# DRIVERS_CONNECTORS.net
KiCad netlist of a schematic drawn in Altium Designer
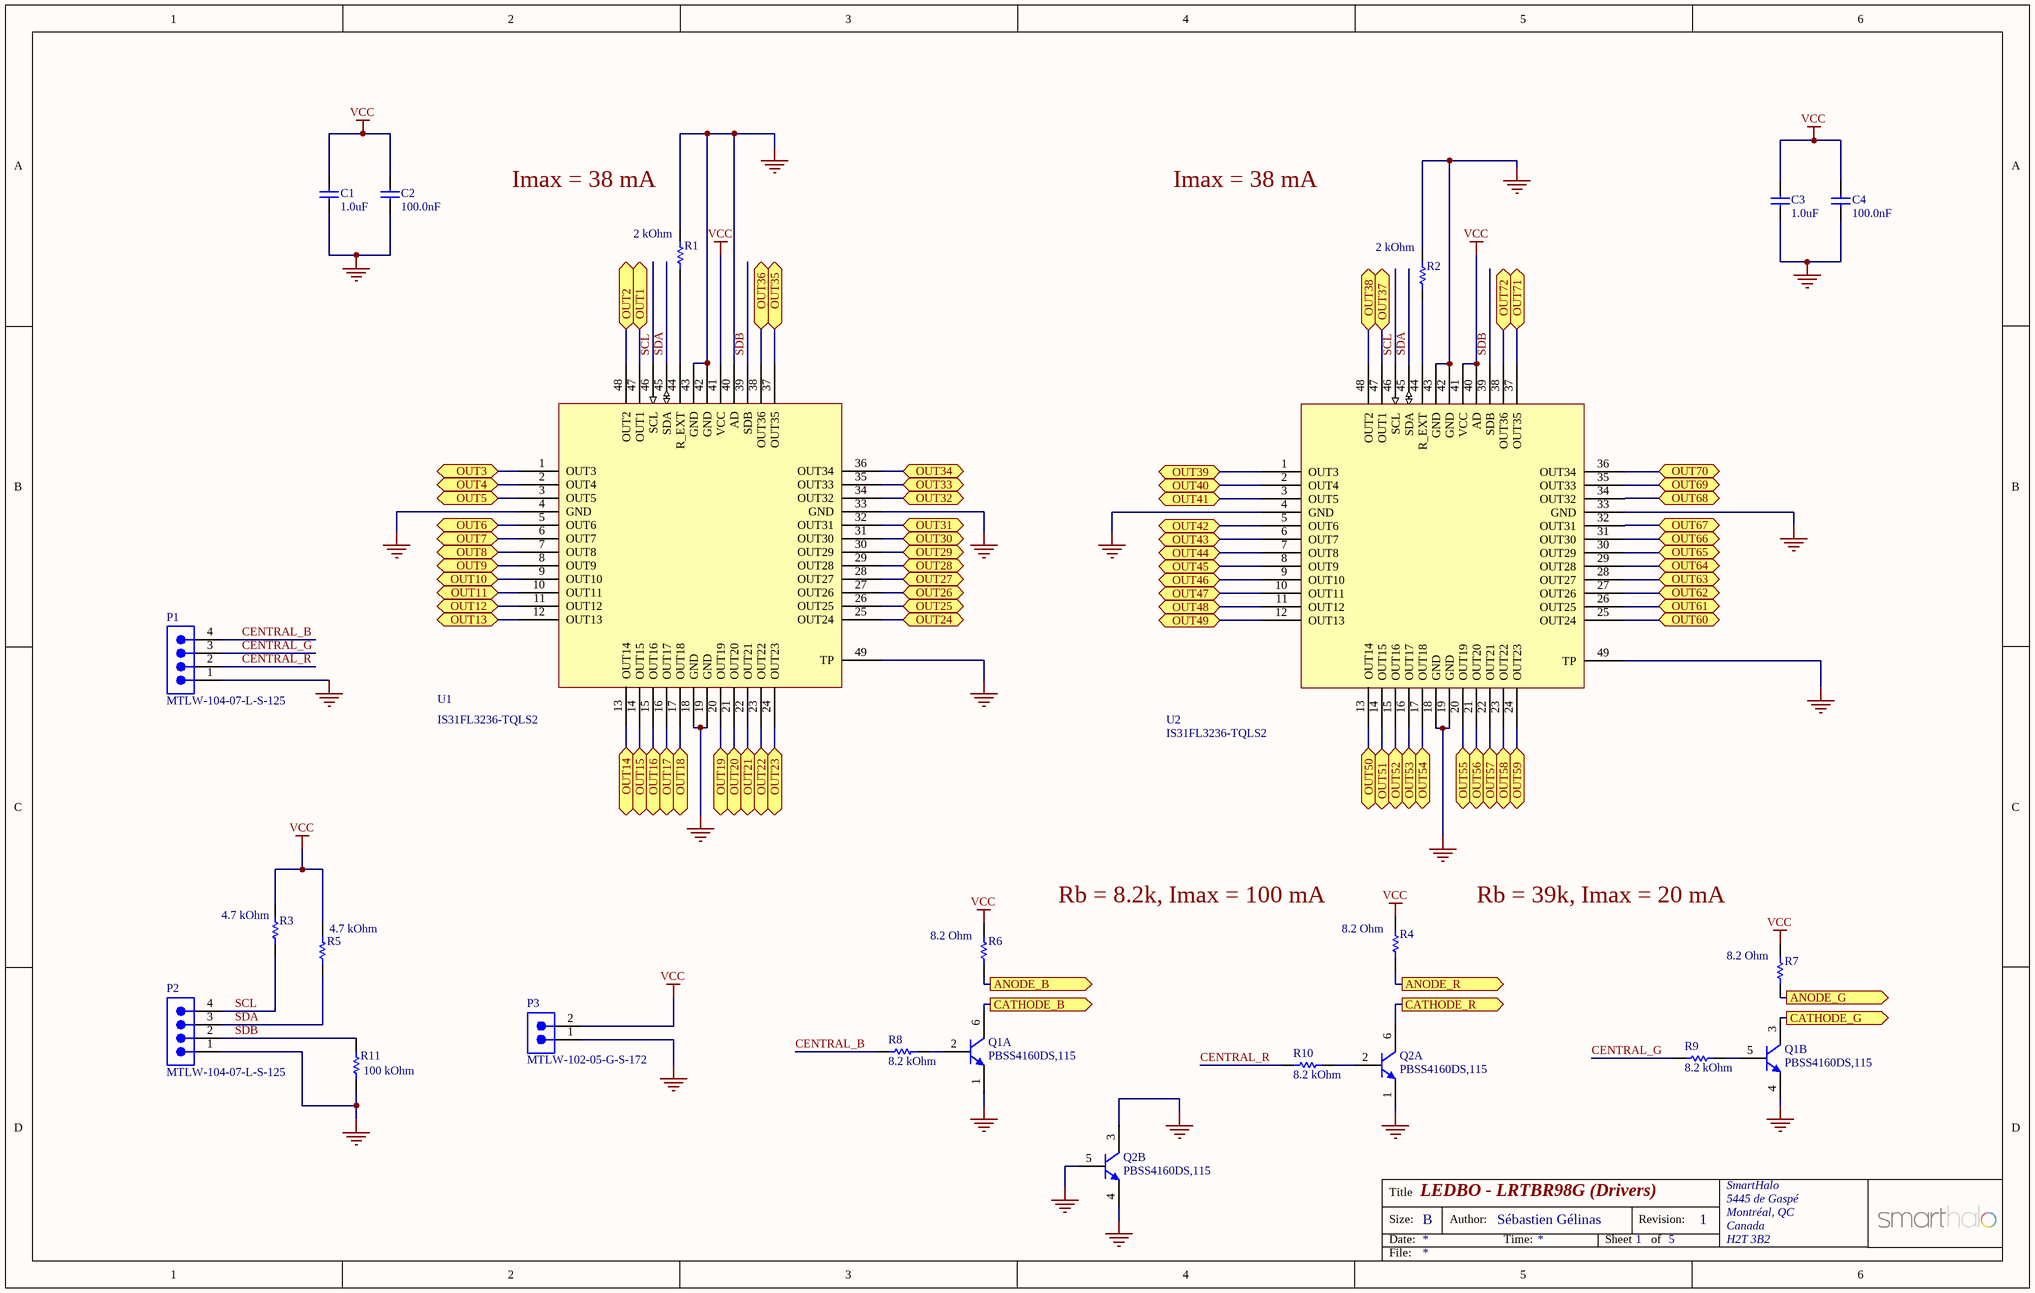
[diagram p0: DRIVERS_CONNECTORS.SchDoc]

(export (version "E")
  (design (tool "Eeschema 10.0.6"))
  (components
    (comp (ref "C1")
      (value "1.0uF")
      (footprint "CAPC0603(1608)100_N")
      (description "Chip Cap 0603 X7R 10%")
      (fields (field (name "PART NUMBER") "C0402-1n0") (field (name "PUBLISHER") "Nordic Semiconductor"))
      (libsource (lib "SmartHalo") (part "CAP0603"))
    )
    (comp (ref "C2")
      (value "100.0nF")
      (footprint "CAPC0603(1608)100_N")
      (description "Chip Cap 0603 X7R 10%")
      (fields (field (name "PART NUMBER") "C0402-1n0") (field (name "PUBLISHER") "Nordic Semiconductor"))
      (libsource (lib "SmartHalo") (part "CAP0603"))
    )
    (comp (ref "C3")
      (value "1.0uF")
      (footprint "CAPC0603(1608)100_N")
      (description "Chip Cap 0603 X7R 10%")
      (fields (field (name "PART NUMBER") "C0402-1n0") (field (name "PUBLISHER") "Nordic Semiconductor"))
      (libsource (lib "SmartHalo") (part "CAP0603"))
    )
    (comp (ref "C4")
      (value "100.0nF")
      (footprint "CAPC0603(1608)100_N")
      (description "Chip Cap 0603 X7R 10%")
      (fields (field (name "PART NUMBER") "C0402-1n0") (field (name "PUBLISHER") "Nordic Semiconductor"))
      (libsource (lib "SmartHalo") (part "CAP0603"))
    )
    (comp (ref "P1")
      (value "MTLW-104-07-L-S-125")
      (footprint "SMTC-MTLW-104-07-X-S-125")
      (fields (field (name "MANUFACTURER") "Samtec"))
      (libsource (lib "Altium Content Vault") (part "CMP-1024-00072-1"))
    )
    (comp (ref "P2")
      (value "MTLW-104-07-L-S-125")
      (footprint "SMTC-MTLW-104-07-X-S-125")
      (fields (field (name "MANUFACTURER") "Samtec"))
      (libsource (lib "Altium Content Vault") (part "CMP-1024-00072-1"))
    )
    (comp (ref "P3")
      (value "MTLW-102-05-G-S-172")
      (footprint "SMTC-MTLW-102-05-X-S-172")
      (fields (field (name "MANUFACTURER") "Samtec"))
      (libsource (lib "Altium Content Vault") (part "CMP-1024-00064-1"))
    )
    (comp (ref "Q1")
      (value "PBSS4160DS,115")
      (footprint "NXP-SC74_M")
      (description "TRANS 2NPN 60V 1A 6TSOP")
      (fields (field (name "PARTNUMBER") "PBSS4160DS") (field (name "MANUFACTURER") "NXP Semiconductors"))
      (libsource (lib "SmartHalo") (part "PBSS4160DS,115"))
    )
    (comp (ref "Q2")
      (value "PBSS4160DS,115")
      (footprint "NXP-SC74_M")
      (description "TRANS 2NPN 60V 1A 6TSOP")
      (fields (field (name "PARTNUMBER") "PBSS4160DS") (field (name "MANUFACTURER") "NXP Semiconductors"))
      (libsource (lib "SmartHalo") (part "PBSS4160DS,115"))
    )
    (comp (ref "R1")
      (value "2 kOhm")
      (footprint "RESC0603(1608)_N")
      (description "2k 0.1W 5% 0603 (1608 Metric)  SMD")
      (fields (field (name "TOLERANCE") "5 %") (field (name "POWER") "0.1 W"))
      (libsource (lib "Altium Content Vault") (part "CMP-1012-00090-1"))
    )
    (comp (ref "R2")
      (value "2 kOhm")
      (footprint "RESC0603(1608)_N")
      (description "2k 0.1W 5% 0603 (1608 Metric)  SMD")
      (fields (field (name "TOLERANCE") "5 %") (field (name "POWER") "0.1 W"))
      (libsource (lib "Altium Content Vault") (part "CMP-1012-00090-1"))
    )
    (comp (ref "R3")
      (value "4.7 kOhm")
      (footprint "RESC0603(1608)_N")
      (description "4K7 0.1W 5% 0603 (1608 Metric)  SMD")
      (fields (field (name "TOLERANCE") "5 %") (field (name "POWER") "0.1 W"))
      (libsource (lib "Altium Content Vault") (part "CMP-1012-00090-1"))
    )
    (comp (ref "R4")
      (value "8.2 Ohm")
      (footprint "RESC0603(1608)_N")
      (description "8R2 0.1W 5% 0603 (1608 Metric)  SMD")
      (fields (field (name "TOLERANCE") "5 %") (field (name "POWER") "0.1 W"))
      (libsource (lib "Altium Content Vault") (part "CMP-1012-00090-1"))
    )
    (comp (ref "R5")
      (value "4.7 kOhm")
      (footprint "RESC0603(1608)_N")
      (description "4K7 0.1W 5% 0603 (1608 Metric)  SMD")
      (fields (field (name "TOLERANCE") "5 %") (field (name "POWER") "0.1 W"))
      (libsource (lib "Altium Content Vault") (part "CMP-1012-00090-1"))
    )
    (comp (ref "R6")
      (value "8.2 Ohm")
      (footprint "RESC0603(1608)_N")
      (description "8R2 0.1W 5% 0603 (1608 Metric)  SMD")
      (fields (field (name "TOLERANCE") "5 %") (field (name "POWER") "0.1 W"))
      (libsource (lib "Altium Content Vault") (part "CMP-1012-00090-1"))
    )
    (comp (ref "R7")
      (value "8.2 Ohm")
      (footprint "RESC0603(1608)_N")
      (description "8R2 0.1W 5% 0603 (1608 Metric)  SMD")
      (fields (field (name "TOLERANCE") "5 %") (field (name "POWER") "0.1 W"))
      (libsource (lib "Altium Content Vault") (part "CMP-1012-00090-1"))
    )
    (comp (ref "R8")
      (value "8.2 kOhm")
      (footprint "RESC0603(1608)_N")
      (description "8K2 0.1W 5% 0603 (1608 Metric)  SMD")
      (fields (field (name "TOLERANCE") "5 %") (field (name "POWER") "0.1 W"))
      (libsource (lib "Altium Content Vault") (part "CMP-1012-00090-1"))
    )
    (comp (ref "R9")
      (value "8.2 kOhm")
      (footprint "RESC0603(1608)_N")
      (description "8K2 0.1W 5% 0603 (1608 Metric)  SMD")
      (fields (field (name "TOLERANCE") "5 %") (field (name "POWER") "0.1 W"))
      (libsource (lib "Altium Content Vault") (part "CMP-1012-00090-1"))
    )
    (comp (ref "R10")
      (value "8.2 kOhm")
      (footprint "RESC0603(1608)_N")
      (description "8K2 0.1W 5% 0603 (1608 Metric)  SMD")
      (fields (field (name "TOLERANCE") "5 %") (field (name "POWER") "0.1 W"))
      (libsource (lib "Altium Content Vault") (part "CMP-1012-00090-1"))
    )
    (comp (ref "R11")
      (value "100 kOhm")
      (footprint "RESC0603(1608)_N")
      (description "100k 0.1W 5% 0603 (1608 Metric)  SMD")
      (fields (field (name "TOLERANCE") "5 %") (field (name "POWER") "0.1 W"))
      (libsource (lib "Altium Content Vault") (part "CMP-1012-00090-1"))
    )
    (comp (ref "U1")
      (value "IS31FL3236-TQLS2")
      (footprint "TQFP48")
      (description "IC 36 CHANNELS LED DRIVER")
      (fields (field (name "MANUFACTURER") "ISSI"))
      (libsource (lib "SmartHalo") (part "IS31FL3236-TQLS2"))
    )
    (comp (ref "U2")
      (value "IS31FL3236-TQLS2")
      (footprint "TQFP48")
      (description "IC 36 CHANNELS LED DRIVER")
      (fields (field (name "MANUFACTURER") "ISSI"))
      (libsource (lib "SmartHalo") (part "IS31FL3236-TQLS2"))
    )
  )
  (nets
    (net (code "1") (name "/ANODE_B") (class "Default")
      (node (ref "R6") (pin "1") (pinfunction "1_1") (pintype "passive"))
    )
    (net (code "2") (name "/ANODE_G") (class "Default")
      (node (ref "R7") (pin "1") (pinfunction "1_1") (pintype "passive"))
    )
    (net (code "3") (name "/ANODE_R") (class "Default")
      (node (ref "R4") (pin "1") (pinfunction "1_1") (pintype "passive"))
    )
    (net (code "4") (name "/CATHODE_B") (class "Default")
      (node (ref "Q1") (pin "6") (pinfunction "C1_6") (pintype "passive"))
    )
    (net (code "5") (name "/CATHODE_G") (class "Default")
      (node (ref "Q1") (pin "3") (pinfunction "C2_3") (pintype "passive"))
    )
    (net (code "6") (name "/CATHODE_R") (class "Default")
      (node (ref "Q2") (pin "6") (pinfunction "C1_6") (pintype "passive"))
    )
    (net (code "7") (name "/CENTRAL_B") (class "Default")
      (node (ref "P1") (pin "4") (pinfunction "4_4") (pintype "passive"))
      (node (ref "R8") (pin "2") (pinfunction "2_2") (pintype "passive"))
    )
    (net (code "8") (name "/CENTRAL_G") (class "Default")
      (node (ref "P1") (pin "3") (pinfunction "3_3") (pintype "passive"))
      (node (ref "R9") (pin "2") (pinfunction "2_2") (pintype "passive"))
    )
    (net (code "9") (name "/CENTRAL_R") (class "Default")
      (node (ref "P1") (pin "2") (pinfunction "2_2") (pintype "passive"))
      (node (ref "R10") (pin "2") (pinfunction "2_2") (pintype "passive"))
    )
    (net (code "10") (name "/OUT1") (class "Default")
      (node (ref "U1") (pin "47") (pinfunction "OUT1_47") (pintype "passive"))
    )
    (net (code "11") (name "/OUT2") (class "Default")
      (node (ref "U1") (pin "48") (pinfunction "OUT2_48") (pintype "passive"))
    )
    (net (code "12") (name "/OUT3") (class "Default")
      (node (ref "U1") (pin "1") (pinfunction "OUT3_1") (pintype "passive"))
    )
    (net (code "13") (name "/OUT4") (class "Default")
      (node (ref "U1") (pin "2") (pinfunction "OUT4_2") (pintype "passive"))
    )
    (net (code "14") (name "/OUT5") (class "Default")
      (node (ref "U1") (pin "3") (pinfunction "OUT5_3") (pintype "passive"))
    )
    (net (code "15") (name "/OUT6") (class "Default")
      (node (ref "U1") (pin "5") (pinfunction "OUT6_5") (pintype "passive"))
    )
    (net (code "16") (name "/OUT7") (class "Default")
      (node (ref "U1") (pin "6") (pinfunction "OUT7_6") (pintype "passive"))
    )
    (net (code "17") (name "/OUT8") (class "Default")
      (node (ref "U1") (pin "7") (pinfunction "OUT8_7") (pintype "passive"))
    )
    (net (code "18") (name "/OUT9") (class "Default")
      (node (ref "U1") (pin "8") (pinfunction "OUT9_8") (pintype "passive"))
    )
    (net (code "19") (name "/OUT10") (class "Default")
      (node (ref "U1") (pin "9") (pinfunction "OUT10_9") (pintype "passive"))
    )
    (net (code "20") (name "/OUT11") (class "Default")
      (node (ref "U1") (pin "10") (pinfunction "OUT11_10") (pintype "passive"))
    )
    (net (code "21") (name "/OUT12") (class "Default")
      (node (ref "U1") (pin "11") (pinfunction "OUT12_11") (pintype "passive"))
    )
    (net (code "22") (name "/OUT13") (class "Default")
      (node (ref "U1") (pin "12") (pinfunction "OUT13_12") (pintype "passive"))
    )
    (net (code "23") (name "/OUT14") (class "Default")
      (node (ref "U1") (pin "13") (pinfunction "OUT14_13") (pintype "passive"))
    )
    (net (code "24") (name "/OUT15") (class "Default")
      (node (ref "U1") (pin "14") (pinfunction "OUT15_14") (pintype "passive"))
    )
    (net (code "25") (name "/OUT16") (class "Default")
      (node (ref "U1") (pin "15") (pinfunction "OUT16_15") (pintype "passive"))
    )
    (net (code "26") (name "/OUT17") (class "Default")
      (node (ref "U1") (pin "16") (pinfunction "OUT17_16") (pintype "passive"))
    )
    (net (code "27") (name "/OUT18") (class "Default")
      (node (ref "U1") (pin "17") (pinfunction "OUT18_17") (pintype "passive"))
    )
    (net (code "28") (name "/OUT19") (class "Default")
      (node (ref "U1") (pin "20") (pinfunction "OUT19_20") (pintype "passive"))
    )
    (net (code "29") (name "/OUT20") (class "Default")
      (node (ref "U1") (pin "21") (pinfunction "OUT20_21") (pintype "passive"))
    )
    (net (code "30") (name "/OUT21") (class "Default")
      (node (ref "U1") (pin "22") (pinfunction "OUT21_22") (pintype "passive"))
    )
    (net (code "31") (name "/OUT22") (class "Default")
      (node (ref "U1") (pin "23") (pinfunction "OUT22_23") (pintype "passive"))
    )
    (net (code "32") (name "/OUT23") (class "Default")
      (node (ref "U1") (pin "24") (pinfunction "OUT23_24") (pintype "passive"))
    )
    (net (code "33") (name "/OUT24") (class "Default")
      (node (ref "U1") (pin "25") (pinfunction "OUT24_25") (pintype "passive"))
    )
    (net (code "34") (name "/OUT25") (class "Default")
      (node (ref "U1") (pin "26") (pinfunction "OUT25_26") (pintype "passive"))
    )
    (net (code "35") (name "/OUT26") (class "Default")
      (node (ref "U1") (pin "27") (pinfunction "OUT26_27") (pintype "passive"))
    )
    (net (code "36") (name "/OUT27") (class "Default")
      (node (ref "U1") (pin "28") (pinfunction "OUT27_28") (pintype "passive"))
    )
    (net (code "37") (name "/OUT28") (class "Default")
      (node (ref "U1") (pin "29") (pinfunction "OUT28_29") (pintype "passive"))
    )
    (net (code "38") (name "/OUT29") (class "Default")
      (node (ref "U1") (pin "30") (pinfunction "OUT29_30") (pintype "passive"))
    )
    (net (code "39") (name "/OUT30") (class "Default")
      (node (ref "U1") (pin "31") (pinfunction "OUT30_31") (pintype "passive"))
    )
    (net (code "40") (name "/OUT31") (class "Default")
      (node (ref "U1") (pin "32") (pinfunction "OUT31_32") (pintype "passive"))
    )
    (net (code "41") (name "/OUT32") (class "Default")
      (node (ref "U1") (pin "34") (pinfunction "OUT32_34") (pintype "passive"))
    )
    (net (code "42") (name "/OUT33") (class "Default")
      (node (ref "U1") (pin "35") (pinfunction "OUT33_35") (pintype "passive"))
    )
    (net (code "43") (name "/OUT34") (class "Default")
      (node (ref "U1") (pin "36") (pinfunction "OUT34_36") (pintype "passive"))
    )
    (net (code "44") (name "/OUT35") (class "Default")
      (node (ref "U1") (pin "37") (pinfunction "OUT35_37") (pintype "passive"))
    )
    (net (code "45") (name "/OUT36") (class "Default")
      (node (ref "U1") (pin "38") (pinfunction "OUT36_38") (pintype "passive"))
    )
    (net (code "46") (name "/OUT37") (class "Default")
      (node (ref "U2") (pin "47") (pinfunction "OUT1_47") (pintype "passive"))
    )
    (net (code "47") (name "/OUT38") (class "Default")
      (node (ref "U2") (pin "48") (pinfunction "OUT2_48") (pintype "passive"))
    )
    (net (code "48") (name "/OUT39") (class "Default")
      (node (ref "U2") (pin "1") (pinfunction "OUT3_1") (pintype "passive"))
    )
    (net (code "49") (name "/OUT40") (class "Default")
      (node (ref "U2") (pin "2") (pinfunction "OUT4_2") (pintype "passive"))
    )
    (net (code "50") (name "/OUT41") (class "Default")
      (node (ref "U2") (pin "3") (pinfunction "OUT5_3") (pintype "passive"))
    )
    (net (code "51") (name "/OUT42") (class "Default")
      (node (ref "U2") (pin "5") (pinfunction "OUT6_5") (pintype "passive"))
    )
    (net (code "52") (name "/OUT43") (class "Default")
      (node (ref "U2") (pin "6") (pinfunction "OUT7_6") (pintype "passive"))
    )
    (net (code "53") (name "/OUT44") (class "Default")
      (node (ref "U2") (pin "7") (pinfunction "OUT8_7") (pintype "passive"))
    )
    (net (code "54") (name "/OUT45") (class "Default")
      (node (ref "U2") (pin "8") (pinfunction "OUT9_8") (pintype "passive"))
    )
    (net (code "55") (name "/OUT46") (class "Default")
      (node (ref "U2") (pin "9") (pinfunction "OUT10_9") (pintype "passive"))
    )
    (net (code "56") (name "/OUT47") (class "Default")
      (node (ref "U2") (pin "10") (pinfunction "OUT11_10") (pintype "passive"))
    )
    (net (code "57") (name "/OUT48") (class "Default")
      (node (ref "U2") (pin "11") (pinfunction "OUT12_11") (pintype "passive"))
    )
    (net (code "58") (name "/OUT49") (class "Default")
      (node (ref "U2") (pin "12") (pinfunction "OUT13_12") (pintype "passive"))
    )
    (net (code "59") (name "/OUT50") (class "Default")
      (node (ref "U2") (pin "13") (pinfunction "OUT14_13") (pintype "passive"))
    )
    (net (code "60") (name "/OUT51") (class "Default")
      (node (ref "U2") (pin "14") (pinfunction "OUT15_14") (pintype "passive"))
    )
    (net (code "61") (name "/OUT52") (class "Default")
      (node (ref "U2") (pin "15") (pinfunction "OUT16_15") (pintype "passive"))
    )
    (net (code "62") (name "/OUT53") (class "Default")
      (node (ref "U2") (pin "16") (pinfunction "OUT17_16") (pintype "passive"))
    )
    (net (code "63") (name "/OUT54") (class "Default")
      (node (ref "U2") (pin "17") (pinfunction "OUT18_17") (pintype "passive"))
    )
    (net (code "64") (name "/OUT55") (class "Default")
      (node (ref "U2") (pin "20") (pinfunction "OUT19_20") (pintype "passive"))
    )
    (net (code "65") (name "/OUT56") (class "Default")
      (node (ref "U2") (pin "21") (pinfunction "OUT20_21") (pintype "passive"))
    )
    (net (code "66") (name "/OUT57") (class "Default")
      (node (ref "U2") (pin "22") (pinfunction "OUT21_22") (pintype "passive"))
    )
    (net (code "67") (name "/OUT58") (class "Default")
      (node (ref "U2") (pin "23") (pinfunction "OUT22_23") (pintype "passive"))
    )
    (net (code "68") (name "/OUT59") (class "Default")
      (node (ref "U2") (pin "24") (pinfunction "OUT23_24") (pintype "passive"))
    )
    (net (code "69") (name "/OUT60") (class "Default")
      (node (ref "U2") (pin "25") (pinfunction "OUT24_25") (pintype "passive"))
    )
    (net (code "70") (name "/OUT61") (class "Default")
      (node (ref "U2") (pin "26") (pinfunction "OUT25_26") (pintype "passive"))
    )
    (net (code "71") (name "/OUT62") (class "Default")
      (node (ref "U2") (pin "27") (pinfunction "OUT26_27") (pintype "passive"))
    )
    (net (code "72") (name "/OUT63") (class "Default")
      (node (ref "U2") (pin "28") (pinfunction "OUT27_28") (pintype "passive"))
    )
    (net (code "73") (name "/OUT64") (class "Default")
      (node (ref "U2") (pin "29") (pinfunction "OUT28_29") (pintype "passive"))
    )
    (net (code "74") (name "/OUT65") (class "Default")
      (node (ref "U2") (pin "30") (pinfunction "OUT29_30") (pintype "passive"))
    )
    (net (code "75") (name "/OUT66") (class "Default")
      (node (ref "U2") (pin "31") (pinfunction "OUT30_31") (pintype "passive"))
    )
    (net (code "76") (name "/OUT67") (class "Default")
      (node (ref "U2") (pin "32") (pinfunction "OUT31_32") (pintype "passive"))
    )
    (net (code "77") (name "/OUT68") (class "Default")
      (node (ref "U2") (pin "34") (pinfunction "OUT32_34") (pintype "passive"))
    )
    (net (code "78") (name "/OUT69") (class "Default")
      (node (ref "U2") (pin "35") (pinfunction "OUT33_35") (pintype "passive"))
    )
    (net (code "79") (name "/OUT70") (class "Default")
      (node (ref "U2") (pin "36") (pinfunction "OUT34_36") (pintype "passive"))
    )
    (net (code "80") (name "/OUT71") (class "Default")
      (node (ref "U2") (pin "37") (pinfunction "OUT35_37") (pintype "passive"))
    )
    (net (code "81") (name "/OUT72") (class "Default")
      (node (ref "U2") (pin "38") (pinfunction "OUT36_38") (pintype "passive"))
    )
    (net (code "82") (name "/SCL") (class "Default")
      (node (ref "P2") (pin "4") (pinfunction "4_4") (pintype "passive"))
      (node (ref "R3") (pin "1") (pinfunction "1_1") (pintype "passive"))
      (node (ref "U1") (pin "46") (pinfunction "SCL_46") (pintype "input"))
      (node (ref "U2") (pin "46") (pinfunction "SCL_46") (pintype "input"))
    )
    (net (code "83") (name "/SDA") (class "Default")
      (node (ref "P2") (pin "3") (pinfunction "3_3") (pintype "passive"))
      (node (ref "R5") (pin "1") (pinfunction "1_1") (pintype "passive"))
      (node (ref "U1") (pin "45") (pinfunction "SDA_45") (pintype "bidirectional"))
      (node (ref "U2") (pin "45") (pinfunction "SDA_45") (pintype "bidirectional"))
    )
    (net (code "84") (name "/SDB") (class "Default")
      (node (ref "P2") (pin "2") (pinfunction "2_2") (pintype "passive"))
      (node (ref "R11") (pin "2") (pinfunction "2_2") (pintype "passive"))
      (node (ref "U1") (pin "39") (pinfunction "SDB_39") (pintype "passive"))
      (node (ref "U2") (pin "39") (pinfunction "SDB_39") (pintype "passive"))
    )
    (net (code "85") (name "GND") (class "Default")
      (node (ref "C1") (pin "2") (pinfunction "2_2") (pintype "passive"))
      (node (ref "C2") (pin "2") (pinfunction "2_2") (pintype "passive"))
      (node (ref "C3") (pin "2") (pinfunction "2_2") (pintype "passive"))
      (node (ref "C4") (pin "2") (pinfunction "2_2") (pintype "passive"))
      (node (ref "P1") (pin "1") (pinfunction "1_1") (pintype "passive"))
      (node (ref "P2") (pin "1") (pinfunction "1_1") (pintype "passive"))
      (node (ref "P3") (pin "1") (pinfunction "1_1") (pintype "passive"))
      (node (ref "Q1") (pin "1") (pinfunction "E1_1") (pintype "passive"))
      (node (ref "Q1") (pin "4") (pinfunction "E2_4") (pintype "passive"))
      (node (ref "Q2") (pin "1") (pinfunction "E1_1") (pintype "passive"))
      (node (ref "Q2") (pin "3") (pinfunction "C2_3") (pintype "passive"))
      (node (ref "Q2") (pin "4") (pinfunction "E2_4") (pintype "passive"))
      (node (ref "Q2") (pin "5") (pinfunction "B2_5") (pintype "passive"))
      (node (ref "R1") (pin "2") (pinfunction "2_2") (pintype "passive"))
      (node (ref "R11") (pin "1") (pinfunction "1_1") (pintype "passive"))
      (node (ref "R2") (pin "2") (pinfunction "2_2") (pintype "passive"))
      (node (ref "U1") (pin "18") (pinfunction "GND_18") (pintype "power_in"))
      (node (ref "U1") (pin "19") (pinfunction "GND_19") (pintype "power_in"))
      (node (ref "U1") (pin "33") (pinfunction "GND_33") (pintype "power_in"))
      (node (ref "U1") (pin "4") (pinfunction "GND_4") (pintype "power_in"))
      (node (ref "U1") (pin "40") (pinfunction "AD_40") (pintype "passive"))
      (node (ref "U1") (pin "42") (pinfunction "GND_42") (pintype "power_in"))
      (node (ref "U1") (pin "43") (pinfunction "GND_43") (pintype "power_in"))
      (node (ref "U1") (pin "49") (pinfunction "TP_49") (pintype "power_in"))
      (node (ref "U2") (pin "18") (pinfunction "GND_18") (pintype "power_in"))
      (node (ref "U2") (pin "19") (pinfunction "GND_19") (pintype "power_in"))
      (node (ref "U2") (pin "33") (pinfunction "GND_33") (pintype "power_in"))
      (node (ref "U2") (pin "4") (pinfunction "GND_4") (pintype "power_in"))
      (node (ref "U2") (pin "42") (pinfunction "GND_42") (pintype "power_in"))
      (node (ref "U2") (pin "43") (pinfunction "GND_43") (pintype "power_in"))
      (node (ref "U2") (pin "49") (pinfunction "TP_49") (pintype "power_in"))
    )
    (net (code "86") (name "Net-(Q1A-B1)") (class "Default")
      (node (ref "Q1") (pin "2") (pinfunction "B1_2") (pintype "passive"))
      (node (ref "R8") (pin "1") (pinfunction "1_1") (pintype "passive"))
    )
    (net (code "87") (name "Net-(Q1B-B2)") (class "Default")
      (node (ref "Q1") (pin "5") (pinfunction "B2_5") (pintype "passive"))
      (node (ref "R9") (pin "1") (pinfunction "1_1") (pintype "passive"))
    )
    (net (code "88") (name "Net-(Q2A-B1)") (class "Default")
      (node (ref "Q2") (pin "2") (pinfunction "B1_2") (pintype "passive"))
      (node (ref "R10") (pin "1") (pinfunction "1_1") (pintype "passive"))
    )
    (net (code "89") (name "Net-(U1-R_EXT)") (class "Default")
      (node (ref "R1") (pin "1") (pinfunction "1_1") (pintype "passive"))
      (node (ref "U1") (pin "44") (pinfunction "R_EXT_44") (pintype "passive"))
    )
    (net (code "90") (name "Net-(U2-R_EXT)") (class "Default")
      (node (ref "R2") (pin "1") (pinfunction "1_1") (pintype "passive"))
      (node (ref "U2") (pin "44") (pinfunction "R_EXT_44") (pintype "passive"))
    )
    (net (code "91") (name "VCC") (class "Default")
      (node (ref "C1") (pin "1") (pinfunction "1_1") (pintype "passive"))
      (node (ref "C2") (pin "1") (pinfunction "1_1") (pintype "passive"))
      (node (ref "C3") (pin "1") (pinfunction "1_1") (pintype "passive"))
      (node (ref "C4") (pin "1") (pinfunction "1_1") (pintype "passive"))
      (node (ref "P3") (pin "2") (pinfunction "2_2") (pintype "passive"))
      (node (ref "R3") (pin "2") (pinfunction "2_2") (pintype "passive"))
      (node (ref "R4") (pin "2") (pinfunction "2_2") (pintype "passive"))
      (node (ref "R5") (pin "2") (pinfunction "2_2") (pintype "passive"))
      (node (ref "R6") (pin "2") (pinfunction "2_2") (pintype "passive"))
      (node (ref "R7") (pin "2") (pinfunction "2_2") (pintype "passive"))
      (node (ref "U1") (pin "41") (pinfunction "VCC_41") (pintype "power_in"))
      (node (ref "U2") (pin "40") (pinfunction "AD_40") (pintype "passive"))
      (node (ref "U2") (pin "41") (pinfunction "VCC_41") (pintype "power_in"))
    )
  )
)
